# power.net
KiCad netlist of a schematic drawn in Altium Designer
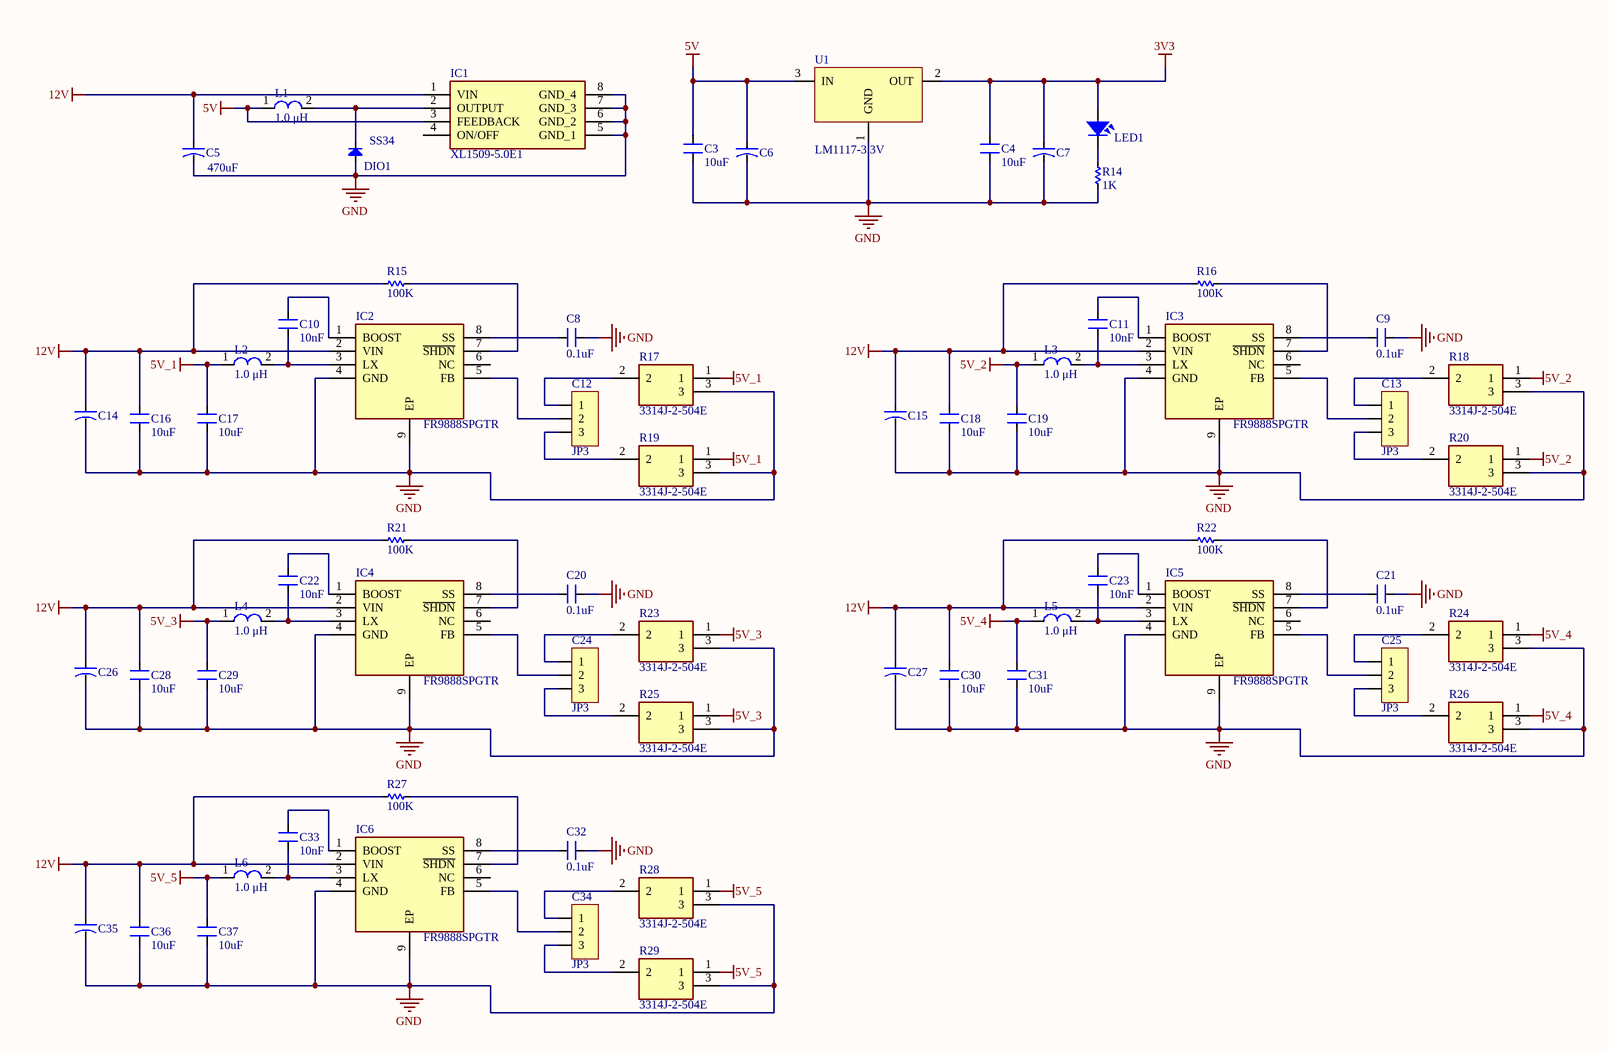
[diagram p0: power.SchDoc]

(export (version "E")
  (design (tool "Eeschema 10.0.6"))
  (components
    (comp (ref "C3")
      (value "10uF")
      (footprint "CN-SMD-0603")
      (description "Tu gom")
      (libsource (lib "LIBTanCN") (part "CN"))
    )
    (comp (ref "C4")
      (value "10uF")
      (footprint "CN-SMD-0603")
      (description "Tu gom")
      (libsource (lib "LIBTanCN") (part "CN"))
    )
    (comp (ref "C5")
      (value "470uF")
      (footprint "CAP-ALU-SMD-6.3x7.7x2.2")
      (description "Polarized Capacitor (Axial)")
      (fields (field (name "PUBLISHER") "Altium Limited"))
      (libsource (lib "LIBTanCN") (part "CN-ALU-SMD"))
    )
    (comp (ref "C6")
      (value "CN-ALU-SMD")
      (footprint "CAP-ALU-SMD-4.5x5x1.4")
      (description "Polarized Capacitor (Axial)")
      (fields (field (name "PUBLISHER") "Altium Limited"))
      (libsource (lib "LIBTanCN") (part "CN-ALU-SMD"))
    )
    (comp (ref "C7")
      (value "CN-ALU-SMD")
      (footprint "CAP-ALU-SMD-4.5x5x1.4")
      (description "Polarized Capacitor (Axial)")
      (fields (field (name "PUBLISHER") "Altium Limited"))
      (libsource (lib "LIBTanCN") (part "CN-ALU-SMD"))
    )
    (comp (ref "C8")
      (value "0.1uF")
      (footprint "CN-SMD-0603")
      (description "Tu gom")
      (libsource (lib "LIBTanCN") (part "CN"))
    )
    (comp (ref "C9")
      (value "0.1uF")
      (footprint "CN-SMD-0603")
      (description "Tu gom")
      (libsource (lib "LIBTanCN") (part "CN"))
    )
    (comp (ref "C10")
      (value "10nF")
      (footprint "CN-SMD-0603")
      (description "Tu gom")
      (libsource (lib "LIBTanCN") (part "CN"))
    )
    (comp (ref "C11")
      (value "10nF")
      (footprint "CN-SMD-0603")
      (description "Tu gom")
      (libsource (lib "LIBTanCN") (part "CN"))
    )
    (comp (ref "C12")
      (value "JP3")
      (footprint "JP3-D1T")
      (description "WR-PHD 2.54 mm Angled Socket Header")
      (fields
        (field (name "MANUFACTURER") "Würth Elektronik eiSos GmbH")
        (field (name "PARTNO") "613003143121")
        (field (name "CREATED BY") "Karrer Zheng")
      )
      (libsource (lib "LIBRARY") (part "JP3"))
    )
    (comp (ref "C13")
      (value "JP3")
      (footprint "JP3-D1T")
      (description "WR-PHD 2.54 mm Angled Socket Header")
      (fields
        (field (name "MANUFACTURER") "Würth Elektronik eiSos GmbH")
        (field (name "PARTNO") "613003143121")
        (field (name "CREATED BY") "Karrer Zheng")
      )
      (libsource (lib "LIBRARY") (part "JP3"))
    )
    (comp (ref "C14")
      (value "CN-ALU-SMD")
      (footprint "CAP-ALU-SMD-4.5x5x1.4")
      (description "Polarized Capacitor (Axial)")
      (fields (field (name "PUBLISHER") "Altium Limited"))
      (libsource (lib "LIBTanCN") (part "CN-ALU-SMD"))
    )
    (comp (ref "C15")
      (value "CN-ALU-SMD")
      (footprint "CAP-ALU-SMD-4.5x5x1.4")
      (description "Polarized Capacitor (Axial)")
      (fields (field (name "PUBLISHER") "Altium Limited"))
      (libsource (lib "LIBTanCN") (part "CN-ALU-SMD"))
    )
    (comp (ref "C16")
      (value "10uF")
      (footprint "CN-SMD-0603")
      (description "Tu gom")
      (libsource (lib "LIBTanCN") (part "CN"))
    )
    (comp (ref "C17")
      (value "10uF")
      (footprint "CN-SMD-0603")
      (description "Tu gom")
      (libsource (lib "LIBTanCN") (part "CN"))
    )
    (comp (ref "C18")
      (value "10uF")
      (footprint "CN-SMD-0603")
      (description "Tu gom")
      (libsource (lib "LIBTanCN") (part "CN"))
    )
    (comp (ref "C19")
      (value "10uF")
      (footprint "CN-SMD-0603")
      (description "Tu gom")
      (libsource (lib "LIBTanCN") (part "CN"))
    )
    (comp (ref "C20")
      (value "0.1uF")
      (footprint "CN-SMD-0603")
      (description "Tu gom")
      (libsource (lib "LIBTanCN") (part "CN"))
    )
    (comp (ref "C21")
      (value "0.1uF")
      (footprint "CN-SMD-0603")
      (description "Tu gom")
      (libsource (lib "LIBTanCN") (part "CN"))
    )
    (comp (ref "C22")
      (value "10nF")
      (footprint "CN-SMD-0603")
      (description "Tu gom")
      (libsource (lib "LIBTanCN") (part "CN"))
    )
    (comp (ref "C23")
      (value "10nF")
      (footprint "CN-SMD-0603")
      (description "Tu gom")
      (libsource (lib "LIBTanCN") (part "CN"))
    )
    (comp (ref "C24")
      (value "JP3")
      (footprint "JP3-D1T")
      (description "WR-PHD 2.54 mm Angled Socket Header")
      (fields
        (field (name "MANUFACTURER") "Würth Elektronik eiSos GmbH")
        (field (name "PARTNO") "613003143121")
        (field (name "CREATED BY") "Karrer Zheng")
      )
      (libsource (lib "LIBRARY") (part "JP3"))
    )
    (comp (ref "C25")
      (value "JP3")
      (footprint "JP3-D1T")
      (description "WR-PHD 2.54 mm Angled Socket Header")
      (fields
        (field (name "MANUFACTURER") "Würth Elektronik eiSos GmbH")
        (field (name "PARTNO") "613003143121")
        (field (name "CREATED BY") "Karrer Zheng")
      )
      (libsource (lib "LIBRARY") (part "JP3"))
    )
    (comp (ref "C26")
      (value "CN-ALU-SMD")
      (footprint "CAP-ALU-SMD-4.5x5x1.4")
      (description "Polarized Capacitor (Axial)")
      (fields (field (name "PUBLISHER") "Altium Limited"))
      (libsource (lib "LIBTanCN") (part "CN-ALU-SMD"))
    )
    (comp (ref "C27")
      (value "CN-ALU-SMD")
      (footprint "CAP-ALU-SMD-4.5x5x1.4")
      (description "Polarized Capacitor (Axial)")
      (fields (field (name "PUBLISHER") "Altium Limited"))
      (libsource (lib "LIBTanCN") (part "CN-ALU-SMD"))
    )
    (comp (ref "C28")
      (value "10uF")
      (footprint "CN-SMD-0603")
      (description "Tu gom")
      (libsource (lib "LIBTanCN") (part "CN"))
    )
    (comp (ref "C29")
      (value "10uF")
      (footprint "CN-SMD-0603")
      (description "Tu gom")
      (libsource (lib "LIBTanCN") (part "CN"))
    )
    (comp (ref "C30")
      (value "10uF")
      (footprint "CN-SMD-0603")
      (description "Tu gom")
      (libsource (lib "LIBTanCN") (part "CN"))
    )
    (comp (ref "C31")
      (value "10uF")
      (footprint "CN-SMD-0603")
      (description "Tu gom")
      (libsource (lib "LIBTanCN") (part "CN"))
    )
    (comp (ref "C32")
      (value "0.1uF")
      (footprint "CN-SMD-0603")
      (description "Tu gom")
      (libsource (lib "LIBTanCN") (part "CN"))
    )
    (comp (ref "C33")
      (value "10nF")
      (footprint "CN-SMD-0603")
      (description "Tu gom")
      (libsource (lib "LIBTanCN") (part "CN"))
    )
    (comp (ref "C34")
      (value "JP3")
      (footprint "JP3-D1T")
      (description "WR-PHD 2.54 mm Angled Socket Header")
      (fields
        (field (name "MANUFACTURER") "Würth Elektronik eiSos GmbH")
        (field (name "PARTNO") "613003143121")
        (field (name "CREATED BY") "Karrer Zheng")
      )
      (libsource (lib "LIBRARY") (part "JP3"))
    )
    (comp (ref "C35")
      (value "CN-ALU-SMD")
      (footprint "CAP-ALU-SMD-4.5x5x1.4")
      (description "Polarized Capacitor (Axial)")
      (fields (field (name "PUBLISHER") "Altium Limited"))
      (libsource (lib "LIBTanCN") (part "CN-ALU-SMD"))
    )
    (comp (ref "C36")
      (value "10uF")
      (footprint "CN-SMD-0603")
      (description "Tu gom")
      (libsource (lib "LIBTanCN") (part "CN"))
    )
    (comp (ref "C37")
      (value "10uF")
      (footprint "CN-SMD-0603")
      (description "Tu gom")
      (libsource (lib "LIBTanCN") (part "CN"))
    )
    (comp (ref "DIO1")
      (value "SS34")
      (footprint "DIO-SMD-106")
      (description "Default Diode")
      (fields (field (name "PUBLISHER") "Altium Limited"))
      (libsource (lib "LIBRARY") (part "Diode SMD"))
    )
    (comp (ref "IC1")
      (value "XL1509-5.0E1")
      (footprint "SamacSys:SOIC127P600X175-8N")
      (description "Integrated Circuit")
      (libsource (lib "SamacSys") (part "XL1509-5.0E1"))
    )
    (comp (ref "IC2")
      (value "FR9888SPGTR")
      (footprint "SamacSys:SOIC127P600X170-9N")
      (description "Integrated Circuit")
      (libsource (lib "*") (part "FR9888SPGTR"))
    )
    (comp (ref "IC3")
      (value "FR9888SPGTR")
      (footprint "SamacSys:SOIC127P600X170-9N")
      (description "Integrated Circuit")
      (libsource (lib "*") (part "FR9888SPGTR"))
    )
    (comp (ref "IC4")
      (value "FR9888SPGTR")
      (footprint "SamacSys:SOIC127P600X170-9N")
      (description "Integrated Circuit")
      (libsource (lib "*") (part "FR9888SPGTR"))
    )
    (comp (ref "IC5")
      (value "FR9888SPGTR")
      (footprint "SamacSys:SOIC127P600X170-9N")
      (description "Integrated Circuit")
      (libsource (lib "*") (part "FR9888SPGTR"))
    )
    (comp (ref "IC6")
      (value "FR9888SPGTR")
      (footprint "SamacSys:SOIC127P600X170-9N")
      (description "Integrated Circuit")
      (libsource (lib "*") (part "FR9888SPGTR"))
    )
    (comp (ref "L1")
      (value "1.0 μH")
      (footprint "L-SMD-M-7.3x4.5")
      (fields
        (field (name "PARTNO") "78477010")
        (field (name "MANUFACTURER") "Wurth Elektronik")
        (field (name "CREATED BY") "Baojun Chen")
      )
      (libsource (lib "LIBTanCN") (part "L-SMD-1"))
    )
    (comp (ref "L2")
      (value "1.0 μH")
      (footprint "L-SMD-M-7.3x4.5")
      (fields
        (field (name "PARTNO") "78477010")
        (field (name "MANUFACTURER") "Wurth Elektronik")
        (field (name "CREATED BY") "Baojun Chen")
      )
      (libsource (lib "LIBRARY") (part "L-SMD-1"))
    )
    (comp (ref "L3")
      (value "1.0 μH")
      (footprint "L-SMD-M-7.3x4.5")
      (fields
        (field (name "PARTNO") "78477010")
        (field (name "MANUFACTURER") "Wurth Elektronik")
        (field (name "CREATED BY") "Baojun Chen")
      )
      (libsource (lib "LIBTanCN") (part "L-SMD-1"))
    )
    (comp (ref "L4")
      (value "1.0 μH")
      (footprint "L-SMD-M-7.3x4.5")
      (fields
        (field (name "PARTNO") "78477010")
        (field (name "MANUFACTURER") "Wurth Elektronik")
        (field (name "CREATED BY") "Baojun Chen")
      )
      (libsource (lib "LIBTanCN") (part "L-SMD-1"))
    )
    (comp (ref "L5")
      (value "1.0 μH")
      (footprint "L-SMD-M-7.3x4.5")
      (fields
        (field (name "PARTNO") "78477010")
        (field (name "MANUFACTURER") "Wurth Elektronik")
        (field (name "CREATED BY") "Baojun Chen")
      )
      (libsource (lib "LIBTanCN") (part "L-SMD-1"))
    )
    (comp (ref "L6")
      (value "1.0 μH")
      (footprint "L-SMD-M-7.3x4.5")
      (fields
        (field (name "PARTNO") "78477010")
        (field (name "MANUFACTURER") "Wurth Elektronik")
        (field (name "CREATED BY") "Baojun Chen")
      )
      (libsource (lib "LIBTanCN") (part "L-SMD-1"))
    )
    (comp (ref "LED1") (value "LED") (footprint "LED-0805-Blue") (libsource (lib "LIBRARY") (part "LED SMD")))
    (comp (ref "R14")
      (value "1K")
      (footprint "RES-SMD-0603")
      (description "Resistor")
      (fields
        (field (name "MANUFACTURER") "Generic Components")
        (field (name "PUBLISHER") "Altium Hobart Technology Centre")
      )
      (libsource (lib "LIBRARY") (part "Res-SMD"))
    )
    (comp (ref "R15")
      (value "100K")
      (footprint "RES-SMD-0603")
      (description "Resistor")
      (fields
        (field (name "MANUFACTURER") "Generic Components")
        (field (name "PUBLISHER") "Altium Hobart Technology Centre")
      )
      (libsource (lib "LIBRARY") (part "Res-SMD"))
    )
    (comp (ref "R16")
      (value "100K")
      (footprint "RES-SMD-0603")
      (description "Resistor")
      (fields
        (field (name "MANUFACTURER") "Generic Components")
        (field (name "PUBLISHER") "Altium Hobart Technology Centre")
      )
      (libsource (lib "LIBRARY") (part "Res-SMD"))
    )
    (comp (ref "R17")
      (value "3314J-2-504E")
      (footprint "SamacSys:3314J-1")
      (description "Resistor")
      (fields (field (name "MOUSER PART NUMBER") "652-3314J-2-504E"))
      (libsource (lib "SamacSys") (part "3314J-2-504E"))
    )
    (comp (ref "R18")
      (value "3314J-2-504E")
      (footprint "SamacSys:3314J-1")
      (description "Resistor")
      (fields (field (name "MOUSER PART NUMBER") "652-3314J-2-504E"))
      (libsource (lib "SamacSys") (part "3314J-2-504E"))
    )
    (comp (ref "R19")
      (value "3314J-2-504E")
      (footprint "SamacSys:3314J-1")
      (description "Resistor")
      (fields (field (name "MOUSER PART NUMBER") "652-3314J-2-504E"))
      (libsource (lib "SamacSys") (part "3314J-2-504E"))
    )
    (comp (ref "R20")
      (value "3314J-2-504E")
      (footprint "SamacSys:3314J-1")
      (description "Resistor")
      (fields (field (name "MOUSER PART NUMBER") "652-3314J-2-504E"))
      (libsource (lib "SamacSys") (part "3314J-2-504E"))
    )
    (comp (ref "R21")
      (value "100K")
      (footprint "RES-SMD-0603")
      (description "Resistor")
      (fields
        (field (name "MANUFACTURER") "Generic Components")
        (field (name "PUBLISHER") "Altium Hobart Technology Centre")
      )
      (libsource (lib "LIBRARY") (part "Res-SMD"))
    )
    (comp (ref "R22")
      (value "100K")
      (footprint "RES-SMD-0603")
      (description "Resistor")
      (fields
        (field (name "MANUFACTURER") "Generic Components")
        (field (name "PUBLISHER") "Altium Hobart Technology Centre")
      )
      (libsource (lib "LIBRARY") (part "Res-SMD"))
    )
    (comp (ref "R23")
      (value "3314J-2-504E")
      (footprint "SamacSys:3314J-1")
      (description "Resistor")
      (fields (field (name "MOUSER PART NUMBER") "652-3314J-2-504E"))
      (libsource (lib "SamacSys") (part "3314J-2-504E"))
    )
    (comp (ref "R24")
      (value "3314J-2-504E")
      (footprint "SamacSys:3314J-1")
      (description "Resistor")
      (fields (field (name "MOUSER PART NUMBER") "652-3314J-2-504E"))
      (libsource (lib "SamacSys") (part "3314J-2-504E"))
    )
    (comp (ref "R25")
      (value "3314J-2-504E")
      (footprint "SamacSys:3314J-1")
      (description "Resistor")
      (fields (field (name "MOUSER PART NUMBER") "652-3314J-2-504E"))
      (libsource (lib "SamacSys") (part "3314J-2-504E"))
    )
    (comp (ref "R26")
      (value "3314J-2-504E")
      (footprint "SamacSys:3314J-1")
      (description "Resistor")
      (fields (field (name "MOUSER PART NUMBER") "652-3314J-2-504E"))
      (libsource (lib "SamacSys") (part "3314J-2-504E"))
    )
    (comp (ref "R27")
      (value "100K")
      (footprint "RES-SMD-0603")
      (description "Resistor")
      (fields
        (field (name "MANUFACTURER") "Generic Components")
        (field (name "PUBLISHER") "Altium Hobart Technology Centre")
      )
      (libsource (lib "LIBRARY") (part "Res-SMD"))
    )
    (comp (ref "R28")
      (value "3314J-2-504E")
      (footprint "SamacSys:3314J-1")
      (description "Resistor")
      (fields (field (name "MOUSER PART NUMBER") "652-3314J-2-504E"))
      (libsource (lib "SamacSys") (part "3314J-2-504E"))
    )
    (comp (ref "R29")
      (value "3314J-2-504E")
      (footprint "SamacSys:3314J-1")
      (description "Resistor")
      (fields (field (name "MOUSER PART NUMBER") "652-3314J-2-504E"))
      (libsource (lib "SamacSys") (part "3314J-2-504E"))
    )
    (comp (ref "U1")
      (value "LM1117-3.3V")
      (footprint "SOT223")
      (description "800mA Low-Dropout Linear Regulator")
      (fields (field (name "CREATOR") "Nguyen Ba Bien"))
      (libsource (lib "LIBRARY") (part "LM1117"))
    )
  )
  (nets
    (net (code "1") (name "3V3") (class "Default")
      (node (ref "C4") (pin "1") (pinfunction "1_1") (pintype "passive"))
      (node (ref "C7") (pin "1") (pinfunction "1_1") (pintype "passive"))
      (node (ref "LED1") (pin "1") (pinfunction "1_1") (pintype "passive"))
      (node (ref "U1") (pin "2") (pinfunction "OUT_2") (pintype "passive"))
    )
    (net (code "2") (name "5V") (class "Default")
      (node (ref "C3") (pin "1") (pinfunction "1_1") (pintype "passive"))
      (node (ref "C6") (pin "1") (pinfunction "1_1") (pintype "passive"))
      (node (ref "IC1") (pin "3") (pinfunction "FEEDBACK_3") (pintype "passive"))
      (node (ref "L1") (pin "1") (pinfunction "1_1") (pintype "passive"))
      (node (ref "U1") (pin "3") (pinfunction "IN_3") (pintype "passive"))
    )
    (net (code "3") (name "5V_1") (class "Default")
      (node (ref "C17") (pin "1") (pinfunction "1_1") (pintype "passive"))
      (node (ref "L2") (pin "1") (pinfunction "1_1") (pintype "passive"))
      (node (ref "R17") (pin "1") (pinfunction "1_1") (pintype "passive"))
      (node (ref "R19") (pin "1") (pinfunction "1_1") (pintype "passive"))
    )
    (net (code "4") (name "5V_2") (class "Default")
      (node (ref "C19") (pin "1") (pinfunction "1_1") (pintype "passive"))
      (node (ref "L3") (pin "1") (pinfunction "1_1") (pintype "passive"))
      (node (ref "R18") (pin "1") (pinfunction "1_1") (pintype "passive"))
      (node (ref "R20") (pin "1") (pinfunction "1_1") (pintype "passive"))
    )
    (net (code "5") (name "5V_3") (class "Default")
      (node (ref "C29") (pin "1") (pinfunction "1_1") (pintype "passive"))
      (node (ref "L4") (pin "1") (pinfunction "1_1") (pintype "passive"))
      (node (ref "R23") (pin "1") (pinfunction "1_1") (pintype "passive"))
      (node (ref "R25") (pin "1") (pinfunction "1_1") (pintype "passive"))
    )
    (net (code "6") (name "5V_4") (class "Default")
      (node (ref "C31") (pin "1") (pinfunction "1_1") (pintype "passive"))
      (node (ref "L5") (pin "1") (pinfunction "1_1") (pintype "passive"))
      (node (ref "R24") (pin "1") (pinfunction "1_1") (pintype "passive"))
      (node (ref "R26") (pin "1") (pinfunction "1_1") (pintype "passive"))
    )
    (net (code "7") (name "5V_5") (class "Default")
      (node (ref "C37") (pin "1") (pinfunction "1_1") (pintype "passive"))
      (node (ref "L6") (pin "1") (pinfunction "1_1") (pintype "passive"))
      (node (ref "R28") (pin "1") (pinfunction "1_1") (pintype "passive"))
      (node (ref "R29") (pin "1") (pinfunction "1_1") (pintype "passive"))
    )
    (net (code "8") (name "12V") (class "Default")
      (node (ref "C14") (pin "1") (pinfunction "1_1") (pintype "passive"))
      (node (ref "C15") (pin "1") (pinfunction "1_1") (pintype "passive"))
      (node (ref "C16") (pin "1") (pinfunction "1_1") (pintype "passive"))
      (node (ref "C18") (pin "1") (pinfunction "1_1") (pintype "passive"))
      (node (ref "C26") (pin "1") (pinfunction "1_1") (pintype "passive"))
      (node (ref "C27") (pin "1") (pinfunction "1_1") (pintype "passive"))
      (node (ref "C28") (pin "1") (pinfunction "1_1") (pintype "passive"))
      (node (ref "C30") (pin "1") (pinfunction "1_1") (pintype "passive"))
      (node (ref "C35") (pin "1") (pinfunction "1_1") (pintype "passive"))
      (node (ref "C36") (pin "1") (pinfunction "1_1") (pintype "passive"))
      (node (ref "C5") (pin "1") (pinfunction "1_1") (pintype "passive"))
      (node (ref "IC1") (pin "1") (pinfunction "VIN_1") (pintype "passive"))
      (node (ref "IC2") (pin "2") (pinfunction "VIN_2") (pintype "passive"))
      (node (ref "IC3") (pin "2") (pinfunction "VIN_2") (pintype "passive"))
      (node (ref "IC4") (pin "2") (pinfunction "VIN_2") (pintype "passive"))
      (node (ref "IC5") (pin "2") (pinfunction "VIN_2") (pintype "passive"))
      (node (ref "IC6") (pin "2") (pinfunction "VIN_2") (pintype "passive"))
      (node (ref "R15") (pin "1") (pinfunction "1_1") (pintype "passive"))
      (node (ref "R16") (pin "1") (pinfunction "1_1") (pintype "passive"))
      (node (ref "R21") (pin "1") (pinfunction "1_1") (pintype "passive"))
      (node (ref "R22") (pin "1") (pinfunction "1_1") (pintype "passive"))
      (node (ref "R27") (pin "1") (pinfunction "1_1") (pintype "passive"))
    )
    (net (code "9") (name "GND") (class "Default")
      (node (ref "C14") (pin "2") (pinfunction "2_2") (pintype "passive"))
      (node (ref "C15") (pin "2") (pinfunction "2_2") (pintype "passive"))
      (node (ref "C16") (pin "2") (pinfunction "2_2") (pintype "passive"))
      (node (ref "C17") (pin "2") (pinfunction "2_2") (pintype "passive"))
      (node (ref "C18") (pin "2") (pinfunction "2_2") (pintype "passive"))
      (node (ref "C19") (pin "2") (pinfunction "2_2") (pintype "passive"))
      (node (ref "C20") (pin "1") (pinfunction "1_1") (pintype "passive"))
      (node (ref "C21") (pin "1") (pinfunction "1_1") (pintype "passive"))
      (node (ref "C26") (pin "2") (pinfunction "2_2") (pintype "passive"))
      (node (ref "C27") (pin "2") (pinfunction "2_2") (pintype "passive"))
      (node (ref "C28") (pin "2") (pinfunction "2_2") (pintype "passive"))
      (node (ref "C29") (pin "2") (pinfunction "2_2") (pintype "passive"))
      (node (ref "C3") (pin "2") (pinfunction "2_2") (pintype "passive"))
      (node (ref "C30") (pin "2") (pinfunction "2_2") (pintype "passive"))
      (node (ref "C31") (pin "2") (pinfunction "2_2") (pintype "passive"))
      (node (ref "C32") (pin "1") (pinfunction "1_1") (pintype "passive"))
      (node (ref "C35") (pin "2") (pinfunction "2_2") (pintype "passive"))
      (node (ref "C36") (pin "2") (pinfunction "2_2") (pintype "passive"))
      (node (ref "C37") (pin "2") (pinfunction "2_2") (pintype "passive"))
      (node (ref "C4") (pin "2") (pinfunction "2_2") (pintype "passive"))
      (node (ref "C5") (pin "2") (pinfunction "2_2") (pintype "passive"))
      (node (ref "C6") (pin "2") (pinfunction "2_2") (pintype "passive"))
      (node (ref "C7") (pin "2") (pinfunction "2_2") (pintype "passive"))
      (node (ref "C8") (pin "1") (pinfunction "1_1") (pintype "passive"))
      (node (ref "C9") (pin "1") (pinfunction "1_1") (pintype "passive"))
      (node (ref "DIO1") (pin "1") (pinfunction "A_1") (pintype "passive"))
      (node (ref "IC1") (pin "5") (pinfunction "GND_1_5") (pintype "passive"))
      (node (ref "IC1") (pin "6") (pinfunction "GND_2_6") (pintype "passive"))
      (node (ref "IC1") (pin "7") (pinfunction "GND_3_7") (pintype "passive"))
      (node (ref "IC1") (pin "8") (pinfunction "GND_4_8") (pintype "passive"))
      (node (ref "IC2") (pin "4") (pinfunction "GND_4") (pintype "passive"))
      (node (ref "IC2") (pin "9") (pinfunction "EP_9") (pintype "passive"))
      (node (ref "IC3") (pin "4") (pinfunction "GND_4") (pintype "passive"))
      (node (ref "IC3") (pin "9") (pinfunction "EP_9") (pintype "passive"))
      (node (ref "IC4") (pin "4") (pinfunction "GND_4") (pintype "passive"))
      (node (ref "IC4") (pin "9") (pinfunction "EP_9") (pintype "passive"))
      (node (ref "IC5") (pin "4") (pinfunction "GND_4") (pintype "passive"))
      (node (ref "IC5") (pin "9") (pinfunction "EP_9") (pintype "passive"))
      (node (ref "IC6") (pin "4") (pinfunction "GND_4") (pintype "passive"))
      (node (ref "IC6") (pin "9") (pinfunction "EP_9") (pintype "passive"))
      (node (ref "R14") (pin "2") (pinfunction "2_2") (pintype "passive"))
      (node (ref "R17") (pin "3") (pinfunction "3_3") (pintype "passive"))
      (node (ref "R18") (pin "3") (pinfunction "3_3") (pintype "passive"))
      (node (ref "R19") (pin "3") (pinfunction "3_3") (pintype "passive"))
      (node (ref "R20") (pin "3") (pinfunction "3_3") (pintype "passive"))
      (node (ref "R23") (pin "3") (pinfunction "3_3") (pintype "passive"))
      (node (ref "R24") (pin "3") (pinfunction "3_3") (pintype "passive"))
      (node (ref "R25") (pin "3") (pinfunction "3_3") (pintype "passive"))
      (node (ref "R26") (pin "3") (pinfunction "3_3") (pintype "passive"))
      (node (ref "R28") (pin "3") (pinfunction "3_3") (pintype "passive"))
      (node (ref "R29") (pin "3") (pinfunction "3_3") (pintype "passive"))
      (node (ref "U1") (pin "1") (pinfunction "GND_1") (pintype "passive"))
    )
    (net (code "10") (name "Net-(C12-Pad1)") (class "Default")
      (node (ref "C12") (pin "1") (pinfunction "1_1") (pintype "passive"))
      (node (ref "R17") (pin "2") (pinfunction "2_2") (pintype "passive"))
    )
    (net (code "11") (name "Net-(C12-Pad3)") (class "Default")
      (node (ref "C12") (pin "3") (pinfunction "3_3") (pintype "passive"))
      (node (ref "R19") (pin "2") (pinfunction "2_2") (pintype "passive"))
    )
    (net (code "12") (name "Net-(C13-Pad1)") (class "Default")
      (node (ref "C13") (pin "1") (pinfunction "1_1") (pintype "passive"))
      (node (ref "R18") (pin "2") (pinfunction "2_2") (pintype "passive"))
    )
    (net (code "13") (name "Net-(C13-Pad3)") (class "Default")
      (node (ref "C13") (pin "3") (pinfunction "3_3") (pintype "passive"))
      (node (ref "R20") (pin "2") (pinfunction "2_2") (pintype "passive"))
    )
    (net (code "14") (name "Net-(C24-Pad1)") (class "Default")
      (node (ref "C24") (pin "1") (pinfunction "1_1") (pintype "passive"))
      (node (ref "R23") (pin "2") (pinfunction "2_2") (pintype "passive"))
    )
    (net (code "15") (name "Net-(C24-Pad3)") (class "Default")
      (node (ref "C24") (pin "3") (pinfunction "3_3") (pintype "passive"))
      (node (ref "R25") (pin "2") (pinfunction "2_2") (pintype "passive"))
    )
    (net (code "16") (name "Net-(C25-Pad1)") (class "Default")
      (node (ref "C25") (pin "1") (pinfunction "1_1") (pintype "passive"))
      (node (ref "R24") (pin "2") (pinfunction "2_2") (pintype "passive"))
    )
    (net (code "17") (name "Net-(C25-Pad3)") (class "Default")
      (node (ref "C25") (pin "3") (pinfunction "3_3") (pintype "passive"))
      (node (ref "R26") (pin "2") (pinfunction "2_2") (pintype "passive"))
    )
    (net (code "18") (name "Net-(C34-Pad1)") (class "Default")
      (node (ref "C34") (pin "1") (pinfunction "1_1") (pintype "passive"))
      (node (ref "R28") (pin "2") (pinfunction "2_2") (pintype "passive"))
    )
    (net (code "19") (name "Net-(C34-Pad3)") (class "Default")
      (node (ref "C34") (pin "3") (pinfunction "3_3") (pintype "passive"))
      (node (ref "R29") (pin "2") (pinfunction "2_2") (pintype "passive"))
    )
    (net (code "20") (name "Net-(DIO1-K)") (class "Default")
      (node (ref "DIO1") (pin "2") (pinfunction "K_2") (pintype "passive"))
      (node (ref "IC1") (pin "2") (pinfunction "OUTPUT_2") (pintype "passive"))
      (node (ref "L1") (pin "2") (pinfunction "2_2") (pintype "passive"))
    )
    (net (code "21") (name "Net-(IC2-BOOST)") (class "Default")
      (node (ref "C10") (pin "2") (pinfunction "2_2") (pintype "passive"))
      (node (ref "IC2") (pin "1") (pinfunction "BOOST_1") (pintype "passive"))
    )
    (net (code "22") (name "Net-(IC2-FB)") (class "Default")
      (node (ref "C12") (pin "2") (pinfunction "2_2") (pintype "passive"))
      (node (ref "IC2") (pin "5") (pinfunction "FB_5") (pintype "passive"))
    )
    (net (code "23") (name "Net-(IC2-LX)") (class "Default")
      (node (ref "C10") (pin "1") (pinfunction "1_1") (pintype "passive"))
      (node (ref "IC2") (pin "3") (pinfunction "LX_3") (pintype "passive"))
      (node (ref "L2") (pin "2") (pinfunction "2_2") (pintype "passive"))
    )
    (net (code "24") (name "Net-(IC2-SS)") (class "Default")
      (node (ref "C8") (pin "2") (pinfunction "2_2") (pintype "passive"))
      (node (ref "IC2") (pin "8") (pinfunction "SS_8") (pintype "passive"))
    )
    (net (code "25") (name "Net-(IC2-~{SHDN})") (class "Default")
      (node (ref "IC2") (pin "7") (pinfunction "~{SHDN}_7") (pintype "passive"))
      (node (ref "R15") (pin "2") (pinfunction "2_2") (pintype "passive"))
    )
    (net (code "26") (name "Net-(IC3-BOOST)") (class "Default")
      (node (ref "C11") (pin "2") (pinfunction "2_2") (pintype "passive"))
      (node (ref "IC3") (pin "1") (pinfunction "BOOST_1") (pintype "passive"))
    )
    (net (code "27") (name "Net-(IC3-FB)") (class "Default")
      (node (ref "C13") (pin "2") (pinfunction "2_2") (pintype "passive"))
      (node (ref "IC3") (pin "5") (pinfunction "FB_5") (pintype "passive"))
    )
    (net (code "28") (name "Net-(IC3-LX)") (class "Default")
      (node (ref "C11") (pin "1") (pinfunction "1_1") (pintype "passive"))
      (node (ref "IC3") (pin "3") (pinfunction "LX_3") (pintype "passive"))
      (node (ref "L3") (pin "2") (pinfunction "2_2") (pintype "passive"))
    )
    (net (code "29") (name "Net-(IC3-SS)") (class "Default")
      (node (ref "C9") (pin "2") (pinfunction "2_2") (pintype "passive"))
      (node (ref "IC3") (pin "8") (pinfunction "SS_8") (pintype "passive"))
    )
    (net (code "30") (name "Net-(IC3-~{SHDN})") (class "Default")
      (node (ref "IC3") (pin "7") (pinfunction "~{SHDN}_7") (pintype "passive"))
      (node (ref "R16") (pin "2") (pinfunction "2_2") (pintype "passive"))
    )
    (net (code "31") (name "Net-(IC4-BOOST)") (class "Default")
      (node (ref "C22") (pin "2") (pinfunction "2_2") (pintype "passive"))
      (node (ref "IC4") (pin "1") (pinfunction "BOOST_1") (pintype "passive"))
    )
    (net (code "32") (name "Net-(IC4-FB)") (class "Default")
      (node (ref "C24") (pin "2") (pinfunction "2_2") (pintype "passive"))
      (node (ref "IC4") (pin "5") (pinfunction "FB_5") (pintype "passive"))
    )
    (net (code "33") (name "Net-(IC4-LX)") (class "Default")
      (node (ref "C22") (pin "1") (pinfunction "1_1") (pintype "passive"))
      (node (ref "IC4") (pin "3") (pinfunction "LX_3") (pintype "passive"))
      (node (ref "L4") (pin "2") (pinfunction "2_2") (pintype "passive"))
    )
    (net (code "34") (name "Net-(IC4-SS)") (class "Default")
      (node (ref "C20") (pin "2") (pinfunction "2_2") (pintype "passive"))
      (node (ref "IC4") (pin "8") (pinfunction "SS_8") (pintype "passive"))
    )
    (net (code "35") (name "Net-(IC4-~{SHDN})") (class "Default")
      (node (ref "IC4") (pin "7") (pinfunction "~{SHDN}_7") (pintype "passive"))
      (node (ref "R21") (pin "2") (pinfunction "2_2") (pintype "passive"))
    )
    (net (code "36") (name "Net-(IC5-BOOST)") (class "Default")
      (node (ref "C23") (pin "2") (pinfunction "2_2") (pintype "passive"))
      (node (ref "IC5") (pin "1") (pinfunction "BOOST_1") (pintype "passive"))
    )
    (net (code "37") (name "Net-(IC5-FB)") (class "Default")
      (node (ref "C25") (pin "2") (pinfunction "2_2") (pintype "passive"))
      (node (ref "IC5") (pin "5") (pinfunction "FB_5") (pintype "passive"))
    )
    (net (code "38") (name "Net-(IC5-LX)") (class "Default")
      (node (ref "C23") (pin "1") (pinfunction "1_1") (pintype "passive"))
      (node (ref "IC5") (pin "3") (pinfunction "LX_3") (pintype "passive"))
      (node (ref "L5") (pin "2") (pinfunction "2_2") (pintype "passive"))
    )
    (net (code "39") (name "Net-(IC5-SS)") (class "Default")
      (node (ref "C21") (pin "2") (pinfunction "2_2") (pintype "passive"))
      (node (ref "IC5") (pin "8") (pinfunction "SS_8") (pintype "passive"))
    )
    (net (code "40") (name "Net-(IC5-~{SHDN})") (class "Default")
      (node (ref "IC5") (pin "7") (pinfunction "~{SHDN}_7") (pintype "passive"))
      (node (ref "R22") (pin "2") (pinfunction "2_2") (pintype "passive"))
    )
    (net (code "41") (name "Net-(IC6-BOOST)") (class "Default")
      (node (ref "C33") (pin "2") (pinfunction "2_2") (pintype "passive"))
      (node (ref "IC6") (pin "1") (pinfunction "BOOST_1") (pintype "passive"))
    )
    (net (code "42") (name "Net-(IC6-FB)") (class "Default")
      (node (ref "C34") (pin "2") (pinfunction "2_2") (pintype "passive"))
      (node (ref "IC6") (pin "5") (pinfunction "FB_5") (pintype "passive"))
    )
    (net (code "43") (name "Net-(IC6-LX)") (class "Default")
      (node (ref "C33") (pin "1") (pinfunction "1_1") (pintype "passive"))
      (node (ref "IC6") (pin "3") (pinfunction "LX_3") (pintype "passive"))
      (node (ref "L6") (pin "2") (pinfunction "2_2") (pintype "passive"))
    )
    (net (code "44") (name "Net-(IC6-SS)") (class "Default")
      (node (ref "C32") (pin "2") (pinfunction "2_2") (pintype "passive"))
      (node (ref "IC6") (pin "8") (pinfunction "SS_8") (pintype "passive"))
    )
    (net (code "45") (name "Net-(IC6-~{SHDN})") (class "Default")
      (node (ref "IC6") (pin "7") (pinfunction "~{SHDN}_7") (pintype "passive"))
      (node (ref "R27") (pin "2") (pinfunction "2_2") (pintype "passive"))
    )
    (net (code "46") (name "Net-(LED1-Pad2)") (class "Default")
      (node (ref "LED1") (pin "2") (pinfunction "2_2") (pintype "passive"))
      (node (ref "R14") (pin "1") (pinfunction "1_1") (pintype "passive"))
    )
    (net (code "47") (name "unconnected-(IC1-ON{slash}OFF-Pad4)") (class "Default")
      (node (ref "IC1") (pin "4") (pinfunction "ON/OFF_4") (pintype "passive"))
    )
    (net (code "48") (name "unconnected-(IC2-NC-Pad6)") (class "Default")
      (node (ref "IC2") (pin "6") (pinfunction "NC_6") (pintype "passive"))
    )
    (net (code "49") (name "unconnected-(IC3-NC-Pad6)") (class "Default")
      (node (ref "IC3") (pin "6") (pinfunction "NC_6") (pintype "passive"))
    )
    (net (code "50") (name "unconnected-(IC4-NC-Pad6)") (class "Default")
      (node (ref "IC4") (pin "6") (pinfunction "NC_6") (pintype "passive"))
    )
    (net (code "51") (name "unconnected-(IC5-NC-Pad6)") (class "Default")
      (node (ref "IC5") (pin "6") (pinfunction "NC_6") (pintype "passive"))
    )
    (net (code "52") (name "unconnected-(IC6-NC-Pad6)") (class "Default")
      (node (ref "IC6") (pin "6") (pinfunction "NC_6") (pintype "passive"))
    )
  )
)
